# mcuModule.net
KiCad netlist of a schematic drawn in EAGLE
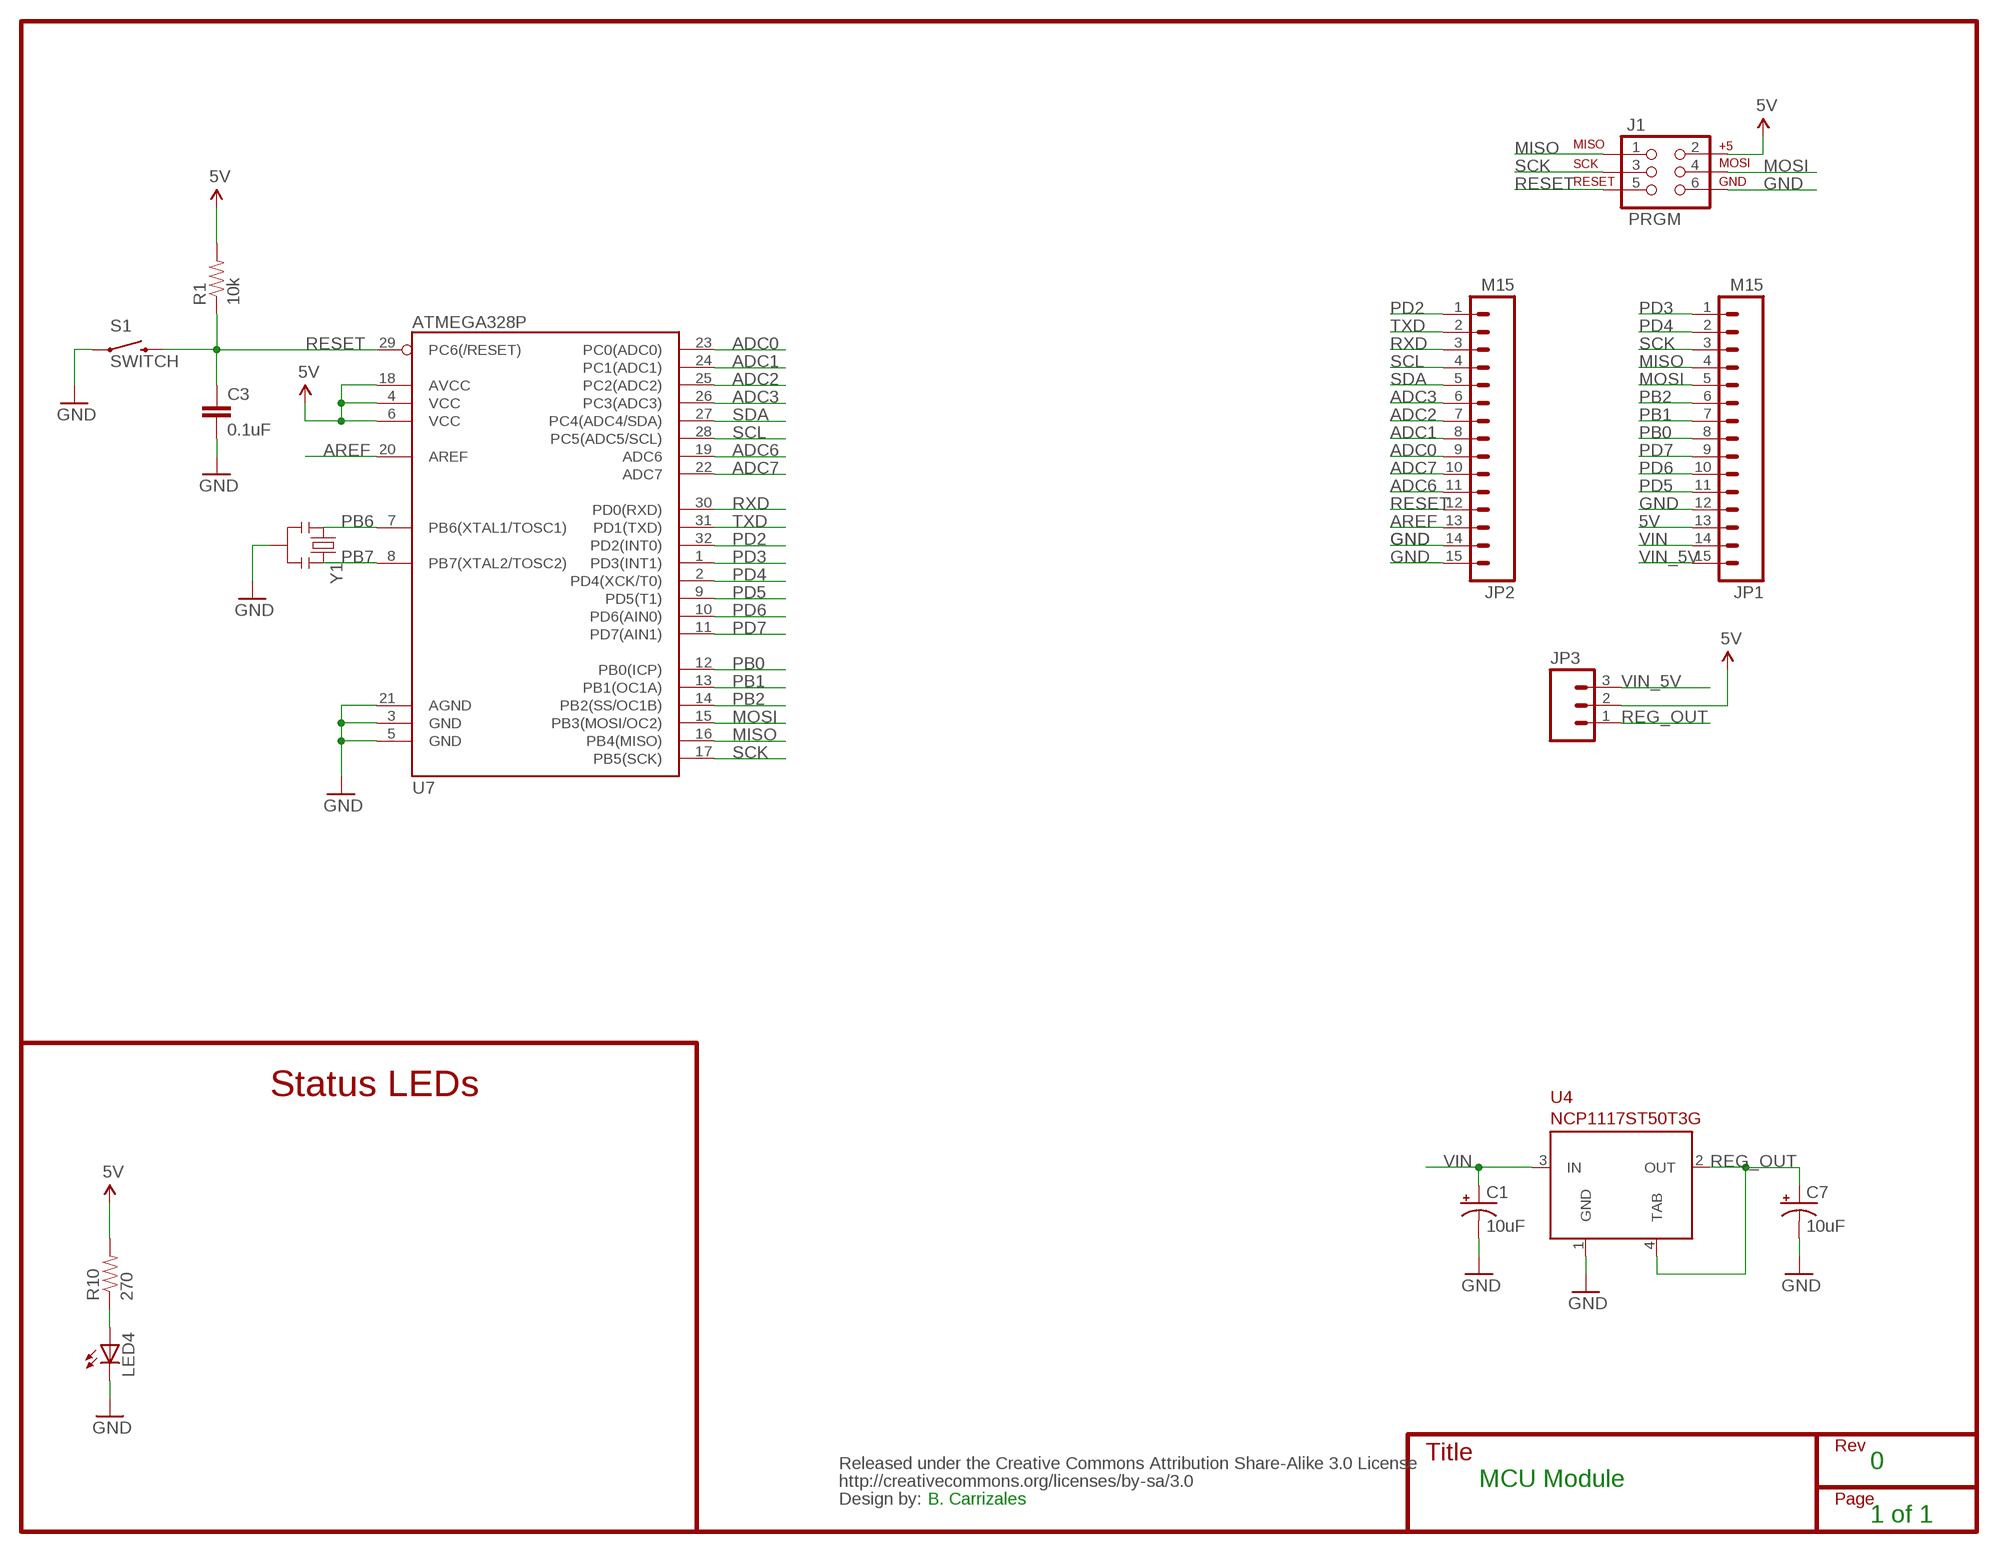
[diagram p0: schematic, sheet 1]

(export (version "E")
  (design (tool "Eeschema 10.0.6"))
  (components
    (comp (ref "C1")
      (value "10uF")
      (footprint "eagle-import:PANASONIC_BMIN")
      (libsource (lib "eagle-import") (part "CAP_POL_AL"))
    )
    (comp (ref "C3")
      (value "0.1uF")
      (footprint "eagle-import:0603-CAP")
      (libsource (lib "eagle-import") (part "CAP0603-CAP"))
    )
    (comp (ref "C7")
      (value "10uF")
      (footprint "eagle-import:PANASONIC_BMIN")
      (libsource (lib "eagle-import") (part "CAP_POL_AL"))
    )
    (comp (ref "CC_TEXT1")
      (value "CREATIVE_COMMONS")
      (footprint "eagle-import:CREATIVE_COMMONS")
      (libsource (lib "eagle-import") (part "CREATIVE_COMMONS"))
    )
    (comp (ref "J1")
      (value "PRGM")
      (footprint "eagle-import:2X3")
      (libsource (lib "eagle-import") (part "AVR_SPI_PRG_6PTH"))
    )
    (comp (ref "JP1")
      (value "M15")
      (footprint "eagle-import:1X15")
      (libsource (lib "eagle-import") (part "M15"))
    )
    (comp (ref "JP2")
      (value "M15")
      (footprint "eagle-import:1X15")
      (libsource (lib "eagle-import") (part "M15"))
    )
    (comp (ref "JP3")
      (value "M03PTH")
      (footprint "eagle-import:1X03")
      (libsource (lib "eagle-import") (part "M03PTH"))
    )
    (comp (ref "LED4")
      (value "LED0603")
      (footprint "eagle-import:LED-0603")
      (libsource (lib "eagle-import") (part "LED0603"))
    )
    (comp (ref "R1")
      (value "10k")
      (footprint "eagle-import:0603-RES")
      (libsource (lib "eagle-import") (part "RESISTOR0603-RES"))
    )
    (comp (ref "R10")
      (value "270")
      (footprint "eagle-import:0603-RES")
      (libsource (lib "eagle-import") (part "RESISTOR0603-RES"))
    )
    (comp (ref "S1")
      (value "SWITCH")
      (footprint "eagle-import:TACTILE_SWITCH_SMD")
      (libsource (lib "eagle-import") (part "SWITCH-MOMENTARY-2SMD"))
    )
    (comp (ref "U4")
      (value "NCP1117ST50T3G")
      (footprint "eagle-import:SOT223")
      (fields (field (name "DIGIKEYPART#") "NCP1117ST50T3GOSCT-ND"))
      (libsource (lib "eagle-import") (part "NCP1117ST50T3G"))
    )
    (comp (ref "U7")
      (value "ATMEGA328P")
      (footprint "eagle-import:TQFP32-08")
      (libsource (lib "eagle-import") (part "ATMEGA328_SMT"))
    )
    (comp (ref "Y1")
      (value "RESONATORPTH")
      (footprint "eagle-import:RESONATOR-PTH")
      (libsource (lib "eagle-import") (part "RESONATORPTH"))
    )
  )
  (nets
    (net (code "1") (name "/ADC0") (class "Default")
      (node (ref "JP2") (pin "9") (pinfunction "9_9") (pintype "passive"))
      (node (ref "U7") (pin "23") (pinfunction "PC0(ADC0)_23") (pintype "bidirectional"))
    )
    (net (code "2") (name "/ADC1") (class "Default")
      (node (ref "JP2") (pin "8") (pinfunction "8_8") (pintype "passive"))
      (node (ref "U7") (pin "24") (pinfunction "PC1(ADC1)_24") (pintype "bidirectional"))
    )
    (net (code "3") (name "/ADC2") (class "Default")
      (node (ref "JP2") (pin "7") (pinfunction "7_7") (pintype "passive"))
      (node (ref "U7") (pin "25") (pinfunction "PC2(ADC2)_25") (pintype "bidirectional"))
    )
    (net (code "4") (name "/ADC3") (class "Default")
      (node (ref "JP2") (pin "6") (pinfunction "6_6") (pintype "passive"))
      (node (ref "U7") (pin "26") (pinfunction "PC3(ADC3)_26") (pintype "bidirectional"))
    )
    (net (code "5") (name "/ADC6") (class "Default")
      (node (ref "JP2") (pin "11") (pinfunction "11_11") (pintype "passive"))
      (node (ref "U7") (pin "19") (pinfunction "ADC6_19") (pintype "bidirectional"))
    )
    (net (code "6") (name "/ADC7") (class "Default")
      (node (ref "JP2") (pin "10") (pinfunction "10_10") (pintype "passive"))
      (node (ref "U7") (pin "22") (pinfunction "ADC7_22") (pintype "bidirectional"))
    )
    (net (code "7") (name "/AREF") (class "Default")
      (node (ref "JP2") (pin "13") (pinfunction "13_13") (pintype "passive"))
      (node (ref "U7") (pin "20") (pinfunction "AREF_20") (pintype "bidirectional"))
    )
    (net (code "8") (name "/MISO") (class "Default")
      (node (ref "J1") (pin "1") (pinfunction "1_1") (pintype "passive"))
      (node (ref "JP1") (pin "4") (pinfunction "4_4") (pintype "passive"))
      (node (ref "U7") (pin "16") (pinfunction "PB4(MISO)_16") (pintype "bidirectional"))
    )
    (net (code "9") (name "/MOSI") (class "Default")
      (node (ref "J1") (pin "4") (pinfunction "4_4") (pintype "passive"))
      (node (ref "JP1") (pin "5") (pinfunction "5_5") (pintype "passive"))
      (node (ref "U7") (pin "15") (pinfunction "PB3(MOSI/OC2)_15") (pintype "bidirectional"))
    )
    (net (code "10") (name "/PB0") (class "Default")
      (node (ref "JP1") (pin "8") (pinfunction "8_8") (pintype "passive"))
      (node (ref "U7") (pin "12") (pinfunction "PB0(ICP)_12") (pintype "bidirectional"))
    )
    (net (code "11") (name "/PB1") (class "Default")
      (node (ref "JP1") (pin "7") (pinfunction "7_7") (pintype "passive"))
      (node (ref "U7") (pin "13") (pinfunction "PB1(OC1A)_13") (pintype "bidirectional"))
    )
    (net (code "12") (name "/PB2") (class "Default")
      (node (ref "JP1") (pin "6") (pinfunction "6_6") (pintype "passive"))
      (node (ref "U7") (pin "14") (pinfunction "PB2(SS/OC1B)_14") (pintype "bidirectional"))
    )
    (net (code "13") (name "/PB6") (class "Default")
      (node (ref "U7") (pin "7") (pinfunction "PB6(XTAL1/TOSC1)_7") (pintype "bidirectional"))
      (node (ref "Y1") (pin "1") (pinfunction "1_1") (pintype "passive"))
    )
    (net (code "14") (name "/PB7") (class "Default")
      (node (ref "U7") (pin "8") (pinfunction "PB7(XTAL2/TOSC2)_8") (pintype "bidirectional"))
      (node (ref "Y1") (pin "3") (pinfunction "3_3") (pintype "passive"))
    )
    (net (code "15") (name "/PD2") (class "Default")
      (node (ref "JP2") (pin "1") (pinfunction "1_1") (pintype "passive"))
      (node (ref "U7") (pin "32") (pinfunction "PD2(INT0)_32") (pintype "bidirectional"))
    )
    (net (code "16") (name "/PD3") (class "Default")
      (node (ref "JP1") (pin "1") (pinfunction "1_1") (pintype "passive"))
      (node (ref "U7") (pin "1") (pinfunction "PD3(INT1)_1") (pintype "bidirectional"))
    )
    (net (code "17") (name "/PD4") (class "Default")
      (node (ref "JP1") (pin "2") (pinfunction "2_2") (pintype "passive"))
      (node (ref "U7") (pin "2") (pinfunction "PD4(XCK/T0)_2") (pintype "bidirectional"))
    )
    (net (code "18") (name "/PD5") (class "Default")
      (node (ref "JP1") (pin "11") (pinfunction "11_11") (pintype "passive"))
      (node (ref "U7") (pin "9") (pinfunction "PD5(T1)_9") (pintype "bidirectional"))
    )
    (net (code "19") (name "/PD6") (class "Default")
      (node (ref "JP1") (pin "10") (pinfunction "10_10") (pintype "passive"))
      (node (ref "U7") (pin "10") (pinfunction "PD6(AIN0)_10") (pintype "bidirectional"))
    )
    (net (code "20") (name "/PD7") (class "Default")
      (node (ref "JP1") (pin "9") (pinfunction "9_9") (pintype "passive"))
      (node (ref "U7") (pin "11") (pinfunction "PD7(AIN1)_11") (pintype "bidirectional"))
    )
    (net (code "21") (name "/REG_OUT") (class "Default")
      (node (ref "C7") (pin "+") (pinfunction "+_+") (pintype "passive"))
      (node (ref "JP3") (pin "1") (pinfunction "1_1") (pintype "passive"))
      (node (ref "U4") (pin "2") (pinfunction "OUT_2") (pintype "bidirectional"))
      (node (ref "U4") (pin "4") (pinfunction "TAB_4") (pintype "bidirectional"))
    )
    (net (code "22") (name "/RESET") (class "Default")
      (node (ref "C3") (pin "1") (pinfunction "1_1") (pintype "passive"))
      (node (ref "J1") (pin "5") (pinfunction "5_5") (pintype "passive"))
      (node (ref "JP2") (pin "12") (pinfunction "12_12") (pintype "passive"))
      (node (ref "R1") (pin "1") (pinfunction "1_1") (pintype "passive"))
      (node (ref "S1") (pin "3") (pinfunction "2_3") (pintype "passive"))
      (node (ref "U7") (pin "29") (pinfunction "PC6(/RESET)_29") (pintype "bidirectional"))
    )
    (net (code "23") (name "/RXD") (class "Default")
      (node (ref "JP2") (pin "3") (pinfunction "3_3") (pintype "passive"))
      (node (ref "U7") (pin "30") (pinfunction "PD0(RXD)_30") (pintype "bidirectional"))
    )
    (net (code "24") (name "/SCK") (class "Default")
      (node (ref "J1") (pin "3") (pinfunction "3_3") (pintype "passive"))
      (node (ref "JP1") (pin "3") (pinfunction "3_3") (pintype "passive"))
      (node (ref "U7") (pin "17") (pinfunction "PB5(SCK)_17") (pintype "bidirectional"))
    )
    (net (code "25") (name "/SCL") (class "Default")
      (node (ref "JP2") (pin "4") (pinfunction "4_4") (pintype "passive"))
      (node (ref "U7") (pin "28") (pinfunction "PC5(ADC5/SCL)_28") (pintype "bidirectional"))
    )
    (net (code "26") (name "/SDA") (class "Default")
      (node (ref "JP2") (pin "5") (pinfunction "5_5") (pintype "passive"))
      (node (ref "U7") (pin "27") (pinfunction "PC4(ADC4/SDA)_27") (pintype "bidirectional"))
    )
    (net (code "27") (name "/TXD") (class "Default")
      (node (ref "JP2") (pin "2") (pinfunction "2_2") (pintype "passive"))
      (node (ref "U7") (pin "31") (pinfunction "PD1(TXD)_31") (pintype "bidirectional"))
    )
    (net (code "28") (name "/VIN") (class "Default")
      (node (ref "C1") (pin "+") (pinfunction "+_+") (pintype "passive"))
      (node (ref "JP1") (pin "14") (pinfunction "14_14") (pintype "passive"))
      (node (ref "U4") (pin "3") (pinfunction "IN_3") (pintype "bidirectional"))
    )
    (net (code "29") (name "/VIN_5V") (class "Default")
      (node (ref "JP1") (pin "15") (pinfunction "15_15") (pintype "passive"))
      (node (ref "JP3") (pin "3") (pinfunction "3_3") (pintype "passive"))
    )
    (net (code "30") (name "5V") (class "Default")
      (node (ref "J1") (pin "2") (pinfunction "2_2") (pintype "passive"))
      (node (ref "JP1") (pin "13") (pinfunction "13_13") (pintype "passive"))
      (node (ref "JP3") (pin "2") (pinfunction "2_2") (pintype "passive"))
      (node (ref "R1") (pin "2") (pinfunction "2_2") (pintype "passive"))
      (node (ref "R10") (pin "2") (pinfunction "2_2") (pintype "passive"))
      (node (ref "U7") (pin "18") (pinfunction "AVCC_18") (pintype "bidirectional"))
      (node (ref "U7") (pin "4") (pinfunction "VCC_4") (pintype "bidirectional"))
      (node (ref "U7") (pin "6") (pinfunction "VCC_6") (pintype "bidirectional"))
    )
    (net (code "31") (name "GND") (class "Default")
      (node (ref "C1") (pin "-") (pinfunction "-_-") (pintype "passive"))
      (node (ref "C3") (pin "2") (pinfunction "2_2") (pintype "passive"))
      (node (ref "C7") (pin "-") (pinfunction "-_-") (pintype "passive"))
      (node (ref "J1") (pin "6") (pinfunction "6_6") (pintype "passive"))
      (node (ref "JP1") (pin "12") (pinfunction "12_12") (pintype "passive"))
      (node (ref "JP2") (pin "14") (pinfunction "14_14") (pintype "passive"))
      (node (ref "JP2") (pin "15") (pinfunction "15_15") (pintype "passive"))
      (node (ref "LED4") (pin "C") (pinfunction "C_C") (pintype "passive"))
      (node (ref "S1") (pin "1") (pinfunction "1_1") (pintype "passive"))
      (node (ref "U4") (pin "1") (pinfunction "GND_1") (pintype "bidirectional"))
      (node (ref "U7") (pin "21") (pinfunction "AGND_21") (pintype "bidirectional"))
      (node (ref "U7") (pin "3") (pinfunction "GND_3") (pintype "bidirectional"))
      (node (ref "U7") (pin "5") (pinfunction "GND_5") (pintype "bidirectional"))
      (node (ref "Y1") (pin "2") (pinfunction "2_2") (pintype "passive"))
    )
    (net (code "32") (name "Net-(LED4-PadA)") (class "Default")
      (node (ref "LED4") (pin "A") (pinfunction "A_A") (pintype "passive"))
      (node (ref "R10") (pin "1") (pinfunction "1_1") (pintype "passive"))
    )
  )
)
